# mosfet-h-bridge-v1-0805.net
KiCad netlist of a schematic drawn in EAGLE
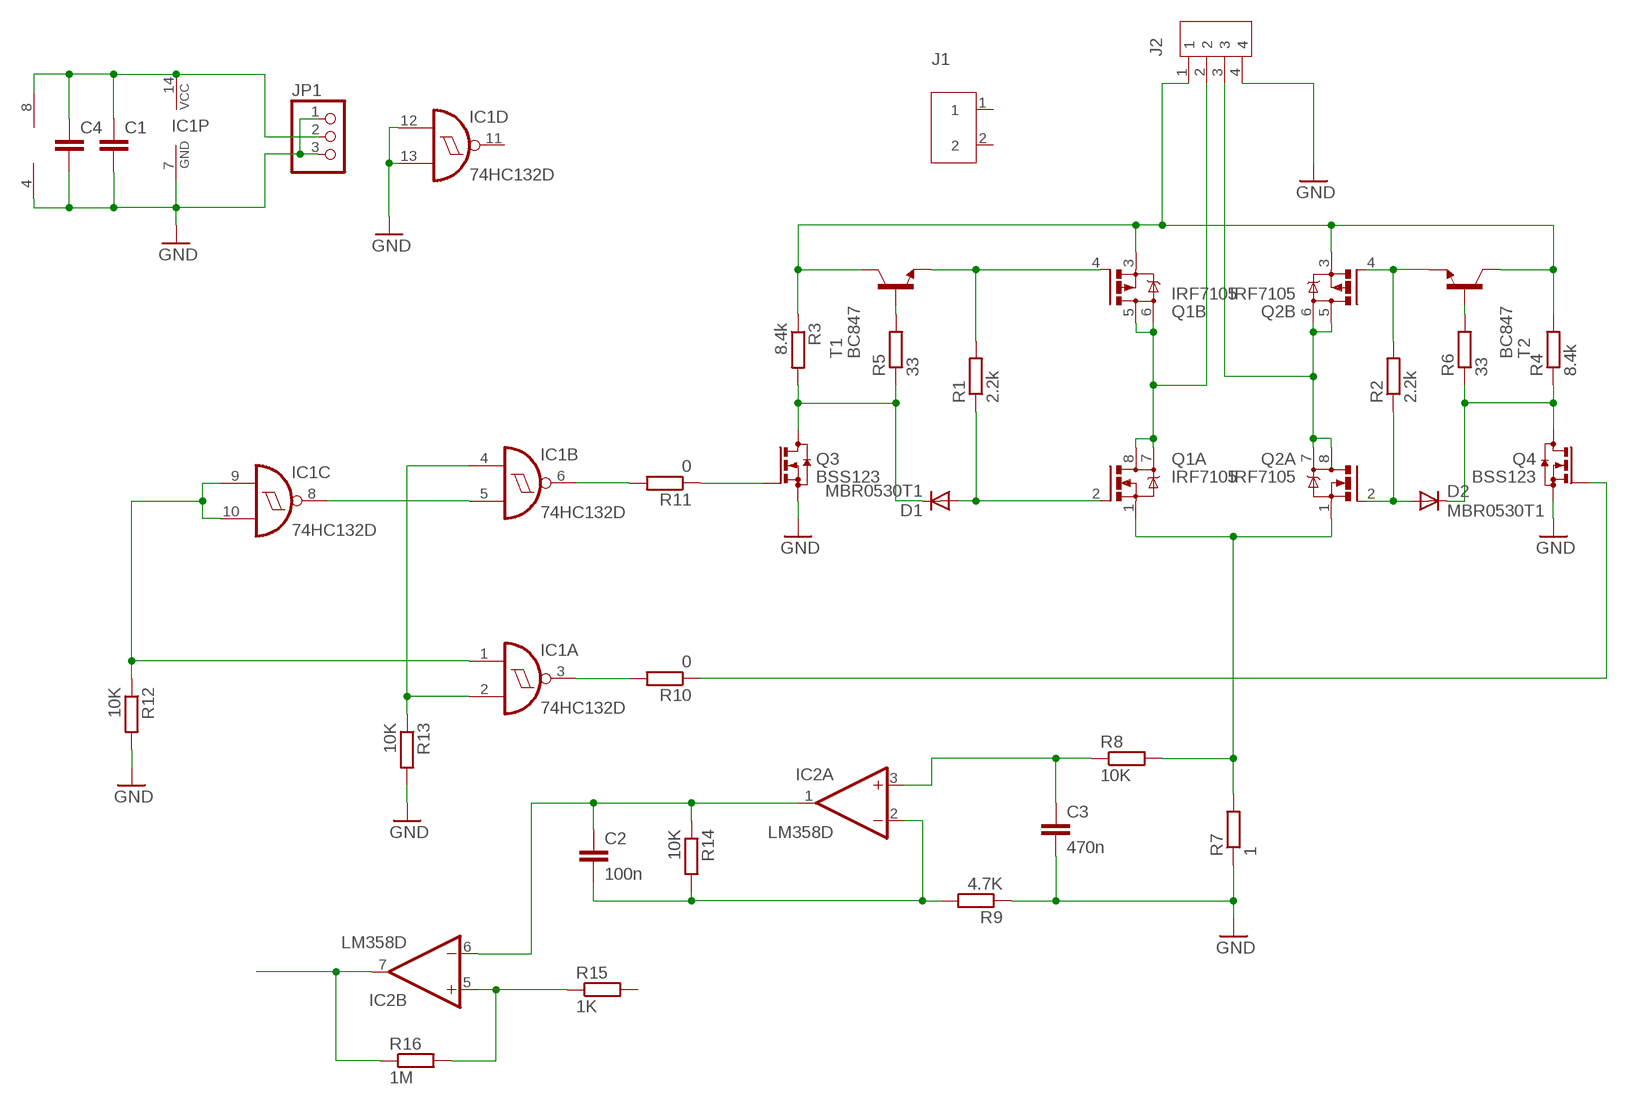
[diagram p0: schematic, sheet 1]

(export (version "E")
  (design (tool "Eeschema 10.0.6"))
  (components
    (comp (ref "C1")
      (value "C-EUC0805")
      (footprint "eagle-import:C0805")
      (libsource (lib "eagle-import") (part "C-EUC0805"))
    )
    (comp (ref "C2")
      (value "100n")
      (footprint "eagle-import:C0805")
      (libsource (lib "eagle-import") (part "C-EUC0805"))
    )
    (comp (ref "C3")
      (value "470n")
      (footprint "eagle-import:C0805")
      (libsource (lib "eagle-import") (part "C-EUC0805"))
    )
    (comp (ref "C4")
      (value "C-EUC0805")
      (footprint "eagle-import:C0805")
      (libsource (lib "eagle-import") (part "C-EUC0805"))
    )
    (comp (ref "D1")
      (value "MBR0530T1")
      (footprint "eagle-import:SOD123")
      (libsource (lib "eagle-import") (part "MBR0530T1"))
    )
    (comp (ref "D2")
      (value "MBR0530T1")
      (footprint "eagle-import:SOD123")
      (libsource (lib "eagle-import") (part "MBR0530T1"))
    )
    (comp (ref "IC1")
      (value "74HC132D")
      (footprint "eagle-import:SO14")
      (libsource (lib "eagle-import") (part "74132DHC"))
    )
    (comp (ref "IC2")
      (value "LM358D")
      (footprint "eagle-import:SO08")
      (libsource (lib "eagle-import") (part "LM358D"))
    )
    (comp (ref "J1")
      (value "SCREW-TERMINAL-2P")
      (footprint "eagle-import:2P-3.36")
      (libsource (lib "eagle-import") (part "SCREW-TERMINAL-2P"))
    )
    (comp (ref "J2")
      (value "SCREW-TERMINAL-4P")
      (footprint "eagle-import:4P-3.36")
      (libsource (lib "eagle-import") (part "SCREW-TERMINAL-4P"))
    )
    (comp (ref "JP1")
      (value "PINHD-1X3")
      (footprint "eagle-import:1X03")
      (libsource (lib "eagle-import") (part "PINHD-1X3"))
    )
    (comp (ref "Q1")
      (value "IRF7105")
      (footprint "eagle-import:SO08")
      (libsource (lib "eagle-import") (part "IRF7105"))
    )
    (comp (ref "Q2")
      (value "IRF7105")
      (footprint "eagle-import:SO08")
      (libsource (lib "eagle-import") (part "IRF7105"))
    )
    (comp (ref "Q3")
      (value "BSS123")
      (footprint "eagle-import:SOT23")
      (libsource (lib "eagle-import") (part "BSS123"))
    )
    (comp (ref "Q4")
      (value "BSS123")
      (footprint "eagle-import:SOT23")
      (libsource (lib "eagle-import") (part "BSS123"))
    )
    (comp (ref "R1")
      (value "2.2k")
      (footprint "eagle-import:R0805")
      (libsource (lib "eagle-import") (part "R-EU_R0805"))
    )
    (comp (ref "R2")
      (value "2.2k")
      (footprint "eagle-import:R0805")
      (libsource (lib "eagle-import") (part "R-EU_R0805"))
    )
    (comp (ref "R3")
      (value "8.4k")
      (footprint "eagle-import:R0805")
      (libsource (lib "eagle-import") (part "R-EU_R0805"))
    )
    (comp (ref "R4")
      (value "8.4k")
      (footprint "eagle-import:R0805")
      (libsource (lib "eagle-import") (part "R-EU_R0805"))
    )
    (comp (ref "R5")
      (value "33")
      (footprint "eagle-import:R0805")
      (libsource (lib "eagle-import") (part "R-EU_R0805"))
    )
    (comp (ref "R6")
      (value "33")
      (footprint "eagle-import:R0805")
      (libsource (lib "eagle-import") (part "R-EU_R0805"))
    )
    (comp (ref "R7")
      (value "1")
      (footprint "eagle-import:R2512")
      (libsource (lib "eagle-import") (part "resistor_R-EU_R2512"))
    )
    (comp (ref "R8")
      (value "10K")
      (footprint "eagle-import:R0805")
      (libsource (lib "eagle-import") (part "R-EU_R0805"))
    )
    (comp (ref "R9")
      (value "4.7K")
      (footprint "eagle-import:R0805")
      (libsource (lib "eagle-import") (part "R-EU_R0805"))
    )
    (comp (ref "R10")
      (value "0")
      (footprint "eagle-import:R0805")
      (libsource (lib "eagle-import") (part "R-EU_R0805"))
    )
    (comp (ref "R11")
      (value "0")
      (footprint "eagle-import:M0805")
      (libsource (lib "eagle-import") (part "R-EU_M0805"))
    )
    (comp (ref "R12")
      (value "10K")
      (footprint "eagle-import:R0805")
      (libsource (lib "eagle-import") (part "R-EU_R0805"))
    )
    (comp (ref "R13")
      (value "10K")
      (footprint "eagle-import:R0805")
      (libsource (lib "eagle-import") (part "R-EU_R0805"))
    )
    (comp (ref "R14")
      (value "10K")
      (footprint "eagle-import:R0805")
      (libsource (lib "eagle-import") (part "R-EU_R0805"))
    )
    (comp (ref "R15")
      (value "1K")
      (footprint "eagle-import:R0805")
      (libsource (lib "eagle-import") (part "R-EU_R0805"))
    )
    (comp (ref "R16")
      (value "1M")
      (footprint "eagle-import:R0805")
      (libsource (lib "eagle-import") (part "R-EU_R0805"))
    )
    (comp (ref "T1")
      (value "BC847")
      (footprint "eagle-import:SOT23")
      (libsource (lib "eagle-import") (part "BC847"))
    )
    (comp (ref "T2")
      (value "BC847")
      (footprint "eagle-import:SOT23")
      (libsource (lib "eagle-import") (part "BC847"))
    )
  )
  (nets
    (net (code "1") (name "GND") (class "Default")
      (node (ref "C1") (pin "2") (pinfunction "2_2") (pintype "passive"))
      (node (ref "C3") (pin "2") (pinfunction "2_2") (pintype "passive"))
      (node (ref "C4") (pin "2") (pinfunction "2_2") (pintype "passive"))
      (node (ref "IC1") (pin "12") (pinfunction "I0_12") (pintype "input"))
      (node (ref "IC1") (pin "13") (pinfunction "I1_13") (pintype "input"))
      (node (ref "IC1") (pin "7") (pinfunction "GND_7") (pintype "power_in"))
      (node (ref "IC2") (pin "4") (pinfunction "V-_4") (pintype "power_in"))
      (node (ref "J2") (pin "4") (pinfunction "4_4") (pintype "bidirectional"))
      (node (ref "JP1") (pin "1") (pinfunction "1_1") (pintype "passive"))
      (node (ref "JP1") (pin "3") (pinfunction "3_3") (pintype "passive"))
      (node (ref "Q3") (pin "2") (pinfunction "S_2") (pintype "passive"))
      (node (ref "Q4") (pin "2") (pinfunction "S_2") (pintype "passive"))
      (node (ref "R12") (pin "2") (pinfunction "2_2") (pintype "passive"))
      (node (ref "R13") (pin "2") (pinfunction "2_2") (pintype "passive"))
      (node (ref "R7") (pin "1") (pinfunction "1_1") (pintype "passive"))
      (node (ref "R9") (pin "1") (pinfunction "1_1") (pintype "passive"))
    )
    (net (code "2") (name "Net-(IC1A-I0)") (class "Default")
      (node (ref "IC1") (pin "1") (pinfunction "I0_1") (pintype "input"))
      (node (ref "IC1") (pin "10") (pinfunction "I1_10") (pintype "input"))
      (node (ref "IC1") (pin "9") (pinfunction "I0_9") (pintype "input"))
      (node (ref "R12") (pin "1") (pinfunction "1_1") (pintype "passive"))
    )
    (net (code "3") (name "Net-(IC1A-I1)") (class "Default")
      (node (ref "IC1") (pin "2") (pinfunction "I1_2") (pintype "input"))
      (node (ref "IC1") (pin "4") (pinfunction "I0_4") (pintype "input"))
      (node (ref "R13") (pin "1") (pinfunction "1_1") (pintype "passive"))
    )
    (net (code "4") (name "Net-(IC1A-O)") (class "Default")
      (node (ref "IC1") (pin "3") (pinfunction "O_3") (pintype "output"))
      (node (ref "R10") (pin "2") (pinfunction "2_2") (pintype "passive"))
    )
    (net (code "5") (name "Net-(IC1B-I1)") (class "Default")
      (node (ref "IC1") (pin "5") (pinfunction "I1_5") (pintype "input"))
      (node (ref "IC1") (pin "8") (pinfunction "O_8") (pintype "output"))
    )
    (net (code "6") (name "Net-(IC1B-O)") (class "Default")
      (node (ref "IC1") (pin "6") (pinfunction "O_6") (pintype "output"))
      (node (ref "R11") (pin "2") (pinfunction "2_2") (pintype "passive"))
    )
    (net (code "7") (name "Net-(IC1E-VCC)") (class "Default")
      (node (ref "C1") (pin "1") (pinfunction "1_1") (pintype "passive"))
      (node (ref "C4") (pin "1") (pinfunction "1_1") (pintype "passive"))
      (node (ref "IC1") (pin "14") (pinfunction "VCC_14") (pintype "power_in"))
      (node (ref "IC2") (pin "8") (pinfunction "V+_8") (pintype "power_in"))
      (node (ref "JP1") (pin "2") (pinfunction "2_2") (pintype "passive"))
    )
    (net (code "8") (name "Net-(IC2A-+IN)") (class "Default")
      (node (ref "C3") (pin "1") (pinfunction "1_1") (pintype "passive"))
      (node (ref "IC2") (pin "3") (pinfunction "+IN_3") (pintype "input"))
      (node (ref "R8") (pin "1") (pinfunction "1_1") (pintype "passive"))
    )
    (net (code "9") (name "Net-(IC2A--IN)") (class "Default")
      (node (ref "C2") (pin "2") (pinfunction "2_2") (pintype "passive"))
      (node (ref "IC2") (pin "2") (pinfunction "-IN_2") (pintype "input"))
      (node (ref "R14") (pin "2") (pinfunction "2_2") (pintype "passive"))
      (node (ref "R9") (pin "2") (pinfunction "2_2") (pintype "passive"))
    )
    (net (code "10") (name "Net-(IC2A-OUT)") (class "Default")
      (node (ref "C2") (pin "1") (pinfunction "1_1") (pintype "passive"))
      (node (ref "IC2") (pin "1") (pinfunction "OUT_1") (pintype "output"))
      (node (ref "IC2") (pin "6") (pinfunction "-IN_6") (pintype "input"))
      (node (ref "R14") (pin "1") (pinfunction "1_1") (pintype "passive"))
    )
    (net (code "11") (name "Net-(IC2B-+IN)") (class "Default")
      (node (ref "IC2") (pin "5") (pinfunction "+IN_5") (pintype "input"))
      (node (ref "R15") (pin "1") (pinfunction "1_1") (pintype "passive"))
      (node (ref "R16") (pin "2") (pinfunction "2_2") (pintype "passive"))
    )
    (net (code "12") (name "Net-(IC2B-OUT)") (class "Default")
      (node (ref "IC2") (pin "7") (pinfunction "OUT_7") (pintype "output"))
      (node (ref "R16") (pin "1") (pinfunction "1_1") (pintype "passive"))
    )
    (net (code "13") (name "Net-(Q1A-D)") (class "Default")
      (node (ref "J2") (pin "2") (pinfunction "2_2") (pintype "bidirectional"))
      (node (ref "Q1") (pin "5") (pinfunction "D_5") (pintype "passive"))
      (node (ref "Q1") (pin "6") (pinfunction "D1_6") (pintype "passive"))
      (node (ref "Q1") (pin "7") (pinfunction "D1_7") (pintype "passive"))
      (node (ref "Q1") (pin "8") (pinfunction "D_8") (pintype "passive"))
    )
    (net (code "14") (name "Net-(Q1A-G)") (class "Default")
      (node (ref "D1") (pin "A") (pinfunction "A_A") (pintype "passive"))
      (node (ref "Q1") (pin "2") (pinfunction "G_2") (pintype "passive"))
      (node (ref "R1") (pin "1") (pinfunction "1_1") (pintype "passive"))
    )
    (net (code "15") (name "Net-(Q1A-S)") (class "Default")
      (node (ref "Q1") (pin "1") (pinfunction "S_1") (pintype "passive"))
      (node (ref "Q2") (pin "1") (pinfunction "S_1") (pintype "passive"))
      (node (ref "R7") (pin "2") (pinfunction "2_2") (pintype "passive"))
      (node (ref "R8") (pin "2") (pinfunction "2_2") (pintype "passive"))
    )
    (net (code "16") (name "Net-(Q1B-G)") (class "Default")
      (node (ref "Q1") (pin "4") (pinfunction "G_4") (pintype "passive"))
      (node (ref "R1") (pin "2") (pinfunction "2_2") (pintype "passive"))
      (node (ref "T1") (pin "2") (pinfunction "E_2") (pintype "passive"))
    )
    (net (code "17") (name "Net-(Q1B-S)") (class "Default")
      (node (ref "J2") (pin "1") (pinfunction "1_1") (pintype "bidirectional"))
      (node (ref "Q1") (pin "3") (pinfunction "S_3") (pintype "passive"))
      (node (ref "Q2") (pin "3") (pinfunction "S_3") (pintype "passive"))
      (node (ref "R3") (pin "1") (pinfunction "1_1") (pintype "passive"))
      (node (ref "R4") (pin "2") (pinfunction "2_2") (pintype "passive"))
      (node (ref "T1") (pin "3") (pinfunction "C_3") (pintype "passive"))
      (node (ref "T2") (pin "3") (pinfunction "C_3") (pintype "passive"))
    )
    (net (code "18") (name "Net-(Q2A-D)") (class "Default")
      (node (ref "J2") (pin "3") (pinfunction "3_3") (pintype "bidirectional"))
      (node (ref "Q2") (pin "5") (pinfunction "D_5") (pintype "passive"))
      (node (ref "Q2") (pin "6") (pinfunction "D1_6") (pintype "passive"))
      (node (ref "Q2") (pin "7") (pinfunction "D1_7") (pintype "passive"))
      (node (ref "Q2") (pin "8") (pinfunction "D_8") (pintype "passive"))
    )
    (net (code "19") (name "Net-(Q2A-G)") (class "Default")
      (node (ref "D2") (pin "A") (pinfunction "A_A") (pintype "passive"))
      (node (ref "Q2") (pin "2") (pinfunction "G_2") (pintype "passive"))
      (node (ref "R2") (pin "1") (pinfunction "1_1") (pintype "passive"))
    )
    (net (code "20") (name "Net-(Q2B-G)") (class "Default")
      (node (ref "Q2") (pin "4") (pinfunction "G_4") (pintype "passive"))
      (node (ref "R2") (pin "2") (pinfunction "2_2") (pintype "passive"))
      (node (ref "T2") (pin "2") (pinfunction "E_2") (pintype "passive"))
    )
    (net (code "21") (name "Net-(Q3-D)") (class "Default")
      (node (ref "D1") (pin "C") (pinfunction "C_C") (pintype "passive"))
      (node (ref "Q3") (pin "3") (pinfunction "D_3") (pintype "passive"))
      (node (ref "R3") (pin "2") (pinfunction "2_2") (pintype "passive"))
      (node (ref "R5") (pin "1") (pinfunction "1_1") (pintype "passive"))
    )
    (net (code "22") (name "Net-(Q3-G)") (class "Default")
      (node (ref "Q3") (pin "1") (pinfunction "G_1") (pintype "passive"))
      (node (ref "R11") (pin "1") (pinfunction "1_1") (pintype "passive"))
    )
    (net (code "23") (name "Net-(Q4-D)") (class "Default")
      (node (ref "D2") (pin "C") (pinfunction "C_C") (pintype "passive"))
      (node (ref "Q4") (pin "3") (pinfunction "D_3") (pintype "passive"))
      (node (ref "R4") (pin "1") (pinfunction "1_1") (pintype "passive"))
      (node (ref "R6") (pin "1") (pinfunction "1_1") (pintype "passive"))
    )
    (net (code "24") (name "Net-(Q4-G)") (class "Default")
      (node (ref "Q4") (pin "1") (pinfunction "G_1") (pintype "passive"))
      (node (ref "R10") (pin "1") (pinfunction "1_1") (pintype "passive"))
    )
    (net (code "25") (name "Net-(T1-B)") (class "Default")
      (node (ref "R5") (pin "2") (pinfunction "2_2") (pintype "passive"))
      (node (ref "T1") (pin "1") (pinfunction "B_1") (pintype "passive"))
    )
    (net (code "26") (name "Net-(T2-B)") (class "Default")
      (node (ref "R6") (pin "2") (pinfunction "2_2") (pintype "passive"))
      (node (ref "T2") (pin "1") (pinfunction "B_1") (pintype "passive"))
    )
    (net (code "27") (name "unconnected-(IC1D-O-Pad11)") (class "Default")
      (node (ref "IC1") (pin "11") (pinfunction "O_11") (pintype "output"))
    )
    (net (code "28") (name "unconnected-(J1-Pad1)") (class "Default")
      (node (ref "J1") (pin "1") (pinfunction "1_1") (pintype "bidirectional"))
    )
    (net (code "29") (name "unconnected-(J1-Pad2)") (class "Default")
      (node (ref "J1") (pin "2") (pinfunction "2_2") (pintype "bidirectional"))
    )
    (net (code "30") (name "unconnected-(R15-Pad2)") (class "Default")
      (node (ref "R15") (pin "2") (pinfunction "2_2") (pintype "passive"))
    )
  )
)
